# YA-S-RaspberryPi-V1_0.net
KiCad netlist of a schematic drawn in Altium Designer
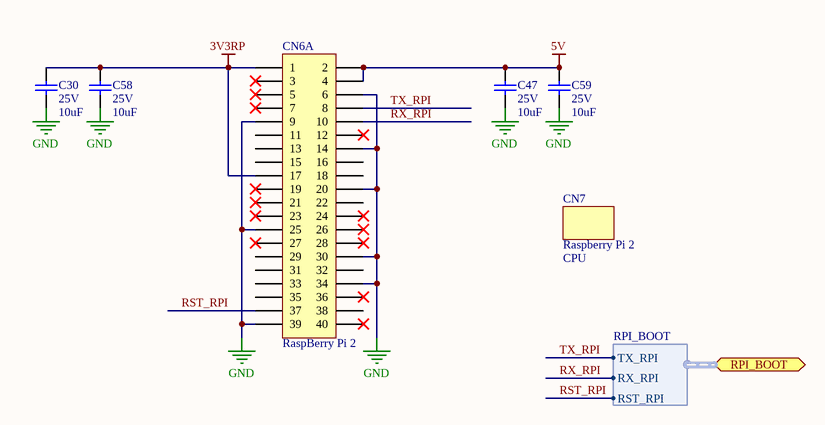
[diagram p0: YA-S-RaspberryPi-V1.0.SchDoc]

(export (version "E")
  (design (tool "Eeschema 10.0.6"))
  (components
    (comp (ref "C30")
      (value "10uF")
      (footprint "CC0805")
      (description "Capacitor (Semiconductor SIM Model)")
      (fields (field (name "TENSÃO") "25V") (field (name "Comment") "Capacitor Cerâmico"))
      (libsource (lib "TecnocladeCAP") (part "Cap 10uF 25V 0805 X5R"))
    )
    (comp (ref "C47")
      (value "10uF")
      (footprint "CC0805")
      (description "Capacitor (Semiconductor SIM Model)")
      (fields (field (name "TENSÃO") "25V") (field (name "Comment") "Capacitor Cerâmico"))
      (libsource (lib "TecnocladeCAP") (part "Cap 10uF 25V 0805 X5R"))
    )
    (comp (ref "C58")
      (value "10uF")
      (footprint "CC0805")
      (description "Capacitor (Semiconductor SIM Model)")
      (fields (field (name "TENSÃO") "25V") (field (name "Comment") "Capacitor Cerâmico"))
      (libsource (lib "TecnocladeCAP") (part "Cap 10uF 25V 0805 X5R"))
    )
    (comp (ref "C59")
      (value "10uF")
      (footprint "CC0805")
      (description "Capacitor (Semiconductor SIM Model)")
      (fields (field (name "TENSÃO") "25V") (field (name "Comment") "Capacitor Cerâmico"))
      (libsource (lib "TecnocladeCAP") (part "Cap 10uF 25V 0805 X5R"))
    )
    (comp (ref "CN6")
      (value "RaspBerry Pi 2")
      (footprint "MOD_RASPBERRY.PI2")
      (description "Modulo RaspBerry Pi 2")
      (libsource (lib "TecnocladeCON") (part "RaspBerry Pi2"))
    )
    (comp (ref "CN7")
      (value "Raspberry Pi 2")
      (footprint "N/A")
      (fields (field (name "ALTIUM_VALUE") "CPU"))
      (libsource (lib "Tecnoclade") (part "Conector Plug"))
    )
  )
  (nets
    (net (code "2") (name "/RST_RPI") (class "Default")
      (node (ref "CN6") (pin "37") (pinfunction "37_37") (pintype "passive"))
    )
    (net (code "3") (name "/RX_RPI") (class "Default")
      (node (ref "CN6") (pin "10") (pinfunction "10_10") (pintype "passive"))
    )
    (net (code "4") (name "/TX_RPI") (class "Default")
      (node (ref "CN6") (pin "8") (pinfunction "8_8") (pintype "passive"))
    )
    (net (code "6") (name "3V3RP") (class "Default")
      (node (ref "C30") (pin "2") (pinfunction "2_2") (pintype "passive"))
      (node (ref "C58") (pin "2") (pinfunction "2_2") (pintype "passive"))
      (node (ref "CN6") (pin "1") (pinfunction "1_1") (pintype "passive"))
      (node (ref "CN6") (pin "17") (pinfunction "17_17") (pintype "passive"))
    )
    (net (code "7") (name "5V") (class "Default")
      (node (ref "C47") (pin "2") (pinfunction "2_2") (pintype "passive"))
      (node (ref "C59") (pin "2") (pinfunction "2_2") (pintype "passive"))
      (node (ref "CN6") (pin "2") (pinfunction "2_2") (pintype "passive"))
      (node (ref "CN6") (pin "4") (pinfunction "4_4") (pintype "passive"))
    )
    (net (code "8") (name "GND") (class "Default")
      (node (ref "C30") (pin "1") (pinfunction "1_1") (pintype "passive"))
      (node (ref "C47") (pin "1") (pinfunction "1_1") (pintype "passive"))
      (node (ref "C58") (pin "1") (pinfunction "1_1") (pintype "passive"))
      (node (ref "C59") (pin "1") (pinfunction "1_1") (pintype "passive"))
      (node (ref "CN6") (pin "14") (pinfunction "14_14") (pintype "passive"))
      (node (ref "CN6") (pin "20") (pinfunction "20_20") (pintype "passive"))
      (node (ref "CN6") (pin "25") (pinfunction "25_25") (pintype "passive"))
      (node (ref "CN6") (pin "30") (pinfunction "30_30") (pintype "passive"))
      (node (ref "CN6") (pin "34") (pinfunction "34_34") (pintype "passive"))
      (node (ref "CN6") (pin "39") (pinfunction "39_39") (pintype "passive"))
      (node (ref "CN6") (pin "6") (pinfunction "6_6") (pintype "passive"))
      (node (ref "CN6") (pin "9") (pinfunction "9_9") (pintype "passive"))
    )
    (net (code "9") (name "unconnected-(CN6-Pad3)") (class "Default")
      (node (ref "CN6") (pin "3") (pinfunction "3_3") (pintype "passive+no_connect"))
    )
    (net (code "10") (name "unconnected-(CN6-Pad5)") (class "Default")
      (node (ref "CN6") (pin "5") (pinfunction "5_5") (pintype "passive+no_connect"))
    )
    (net (code "11") (name "unconnected-(CN6-Pad7)") (class "Default")
      (node (ref "CN6") (pin "7") (pinfunction "7_7") (pintype "passive+no_connect"))
    )
    (net (code "12") (name "unconnected-(CN6-Pad11)") (class "Default")
      (node (ref "CN6") (pin "11") (pinfunction "11_11") (pintype "passive"))
    )
    (net (code "13") (name "unconnected-(CN6-Pad12)") (class "Default")
      (node (ref "CN6") (pin "12") (pinfunction "12_12") (pintype "passive+no_connect"))
    )
    (net (code "14") (name "unconnected-(CN6-Pad13)") (class "Default")
      (node (ref "CN6") (pin "13") (pinfunction "13_13") (pintype "passive"))
    )
    (net (code "15") (name "unconnected-(CN6-Pad15)") (class "Default")
      (node (ref "CN6") (pin "15") (pinfunction "15_15") (pintype "passive"))
    )
    (net (code "16") (name "unconnected-(CN6-Pad16)") (class "Default")
      (node (ref "CN6") (pin "16") (pinfunction "16_16") (pintype "passive"))
    )
    (net (code "17") (name "unconnected-(CN6-Pad18)") (class "Default")
      (node (ref "CN6") (pin "18") (pinfunction "18_18") (pintype "passive"))
    )
    (net (code "18") (name "unconnected-(CN6-Pad19)") (class "Default")
      (node (ref "CN6") (pin "19") (pinfunction "19_19") (pintype "passive+no_connect"))
    )
    (net (code "19") (name "unconnected-(CN6-Pad21)") (class "Default")
      (node (ref "CN6") (pin "21") (pinfunction "21_21") (pintype "passive+no_connect"))
    )
    (net (code "20") (name "unconnected-(CN6-Pad22)") (class "Default")
      (node (ref "CN6") (pin "22") (pinfunction "22_22") (pintype "passive"))
    )
    (net (code "21") (name "unconnected-(CN6-Pad23)") (class "Default")
      (node (ref "CN6") (pin "23") (pinfunction "23_23") (pintype "passive+no_connect"))
    )
    (net (code "22") (name "unconnected-(CN6-Pad24)") (class "Default")
      (node (ref "CN6") (pin "24") (pinfunction "24_24") (pintype "passive+no_connect"))
    )
    (net (code "23") (name "unconnected-(CN6-Pad26)") (class "Default")
      (node (ref "CN6") (pin "26") (pinfunction "26_26") (pintype "passive+no_connect"))
    )
    (net (code "24") (name "unconnected-(CN6-Pad27)") (class "Default")
      (node (ref "CN6") (pin "27") (pinfunction "27_27") (pintype "passive+no_connect"))
    )
    (net (code "25") (name "unconnected-(CN6-Pad28)") (class "Default")
      (node (ref "CN6") (pin "28") (pinfunction "28_28") (pintype "passive+no_connect"))
    )
    (net (code "26") (name "unconnected-(CN6-Pad29)") (class "Default")
      (node (ref "CN6") (pin "29") (pinfunction "29_29") (pintype "passive"))
    )
    (net (code "27") (name "unconnected-(CN6-Pad31)") (class "Default")
      (node (ref "CN6") (pin "31") (pinfunction "31_31") (pintype "passive"))
    )
    (net (code "28") (name "unconnected-(CN6-Pad32)") (class "Default")
      (node (ref "CN6") (pin "32") (pinfunction "32_32") (pintype "passive"))
    )
    (net (code "29") (name "unconnected-(CN6-Pad33)") (class "Default")
      (node (ref "CN6") (pin "33") (pinfunction "33_33") (pintype "passive"))
    )
    (net (code "30") (name "unconnected-(CN6-Pad35)") (class "Default")
      (node (ref "CN6") (pin "35") (pinfunction "35_35") (pintype "passive"))
    )
    (net (code "31") (name "unconnected-(CN6-Pad36)") (class "Default")
      (node (ref "CN6") (pin "36") (pinfunction "36_36") (pintype "passive+no_connect"))
    )
    (net (code "32") (name "unconnected-(CN6-Pad38)") (class "Default")
      (node (ref "CN6") (pin "38") (pinfunction "38_38") (pintype "passive"))
    )
    (net (code "33") (name "unconnected-(CN6-Pad40)") (class "Default")
      (node (ref "CN6") (pin "40") (pinfunction "40_40") (pintype "passive+no_connect"))
    )
  )
)
